# Digital_Io.net
KiCad netlist of a schematic drawn in Altium Designer
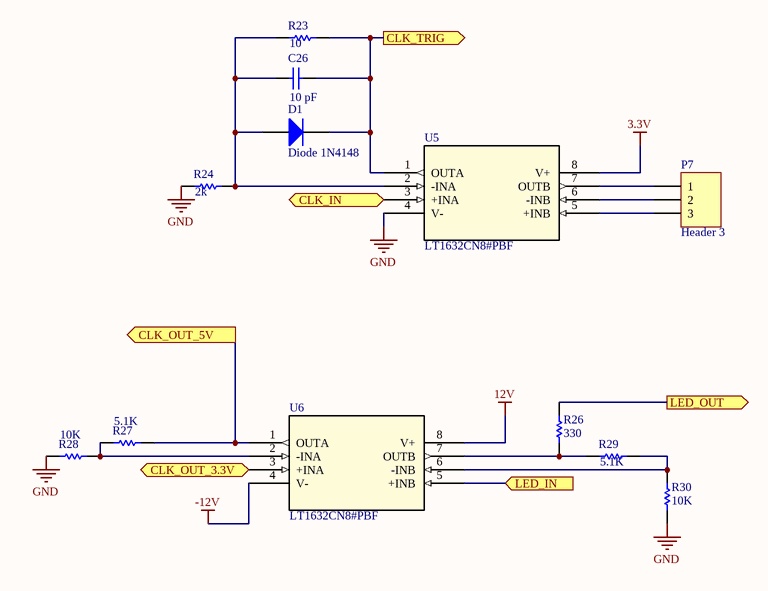
[diagram p0: Digital_Io.SchDoc]

(export (version "E")
  (design (tool "Eeschema 10.0.6"))
  (components
    (comp (ref "C26")
      (value "10 pF")
      (footprint "C0805")
      (description "Capacitor")
      (fields (field (name "PUBLISHER") "Altium Limited"))
      (libsource (lib "Miscellaneous Devices") (part "Cap"))
    )
    (comp (ref "D1")
      (value "Diode 1N4148")
      (footprint "DO-35")
      (description "High Conductance Fast Diode")
      (fields (field (name "PUBLISHER") "Altium Limited"))
      (libsource (lib "Miscellaneous Devices") (part "Diode 1N4148"))
    )
    (comp (ref "P7")
      (value "Header 3")
      (footprint "HDR1X3")
      (description "Header, 3-Pin")
      (fields (field (name "PUBLISHER") "Altium Limited"))
      (libsource (lib "Miscellaneous Connectors") (part "Header 3"))
    )
    (comp (ref "R23")
      (value "10")
      (footprint "AXIAL-0.3")
      (description "Resistor")
      (fields (field (name "Comment") "Res1") (field (name "PUBLISHER") "Altium Limited"))
      (libsource (lib "Miscellaneous Devices") (part "Res1"))
    )
    (comp (ref "R24")
      (value "2k")
      (footprint "AXIAL-0.3")
      (description "Resistor")
      (fields (field (name "Comment") "Res1") (field (name "PUBLISHER") "Altium Limited"))
      (libsource (lib "Miscellaneous Devices") (part "Res1"))
    )
    (comp (ref "R26")
      (value "330")
      (footprint "AXIAL-0.3")
      (description "Resistor")
      (fields (field (name "Comment") "Res1") (field (name "PUBLISHER") "Altium Limited"))
      (libsource (lib "Miscellaneous Devices") (part "Res1"))
    )
    (comp (ref "R27")
      (value "5.1K")
      (footprint "AXIAL-0.3")
      (description "Resistor")
      (fields (field (name "Comment") "Res1") (field (name "PUBLISHER") "Altium Limited"))
      (libsource (lib "Miscellaneous Devices") (part "Res1"))
    )
    (comp (ref "R28")
      (value "10K")
      (footprint "AXIAL-0.3")
      (description "Resistor")
      (fields (field (name "Comment") "Res1") (field (name "PUBLISHER") "Altium Limited"))
      (libsource (lib "Miscellaneous Devices") (part "Res1"))
    )
    (comp (ref "R29")
      (value "5.1K")
      (footprint "AXIAL-0.3")
      (description "Resistor")
      (fields (field (name "Comment") "Res1") (field (name "PUBLISHER") "Altium Limited"))
      (libsource (lib "Miscellaneous Devices") (part "Res1"))
    )
    (comp (ref "R30")
      (value "10K")
      (footprint "AXIAL-0.3")
      (description "Resistor")
      (fields (field (name "Comment") "Res1") (field (name "PUBLISHER") "Altium Limited"))
      (libsource (lib "Miscellaneous Devices") (part "Res1"))
    )
    (comp (ref "U5")
      (value "LT1632CN8#PBF")
      (footprint "PDIP-8_N")
      (description "Imported")
      (fields
        (field (name "DIGIKEYPARTNUMBER") "LT1632CN8-ND")
        (field (name "COPYRIGHT") "Copyright (C) 2015 Accelerated Designs. All rights reserved")
      )
      (libsource (lib "lt1632") (part "LT1632CN8#PBF"))
    )
    (comp (ref "U6")
      (value "LT1632CN8#PBF")
      (footprint "PDIP-8_N")
      (description "Imported")
      (fields
        (field (name "DIGIKEYPARTNUMBER") "LT1632CN8-ND")
        (field (name "COPYRIGHT") "Copyright (C) 2015 Accelerated Designs. All rights reserved")
      )
      (libsource (lib "lt1632") (part "LT1632CN8#PBF"))
    )
  )
  (nets
    (net (code "1") (name "-12V") (class "Default")
      (node (ref "U6") (pin "4") (pinfunction "V-_4") (pintype "power_in"))
    )
    (net (code "2") (name "/CLK_IN") (class "Default")
      (node (ref "U5") (pin "3") (pinfunction "+INA_3") (pintype "input"))
    )
    (net (code "3") (name "/CLK_OUT_3.3V") (class "Default")
      (node (ref "U6") (pin "3") (pinfunction "+INA_3") (pintype "input"))
    )
    (net (code "4") (name "/CLK_OUT_5V") (class "Default")
      (node (ref "R27") (pin "2") (pinfunction "2_2") (pintype "passive"))
      (node (ref "U6") (pin "1") (pinfunction "OUTA_1") (pintype "output"))
    )
    (net (code "5") (name "/CLK_TRIG") (class "Default")
      (node (ref "C26") (pin "1") (pinfunction "1_1") (pintype "passive"))
      (node (ref "D1") (pin "2") (pinfunction "K_2") (pintype "passive"))
      (node (ref "R23") (pin "2") (pinfunction "2_2") (pintype "passive"))
      (node (ref "U5") (pin "1") (pinfunction "OUTA_1") (pintype "output"))
    )
    (net (code "6") (name "/LED_IN") (class "Default")
      (node (ref "U6") (pin "5") (pinfunction "+INB_5") (pintype "input"))
    )
    (net (code "7") (name "/LED_OUT") (class "Default")
      (node (ref "R26") (pin "2") (pinfunction "2_2") (pintype "passive"))
    )
    (net (code "8") (name "3.3V") (class "Default")
      (node (ref "U5") (pin "8") (pinfunction "V+_8") (pintype "power_in"))
    )
    (net (code "9") (name "12V") (class "Default")
      (node (ref "U6") (pin "8") (pinfunction "V+_8") (pintype "power_in"))
    )
    (net (code "10") (name "GND") (class "Default")
      (node (ref "R24") (pin "1") (pinfunction "1_1") (pintype "passive"))
      (node (ref "R28") (pin "1") (pinfunction "1_1") (pintype "passive"))
      (node (ref "R30") (pin "1") (pinfunction "1_1") (pintype "passive"))
      (node (ref "U5") (pin "4") (pinfunction "V-_4") (pintype "power_in"))
    )
    (net (code "11") (name "Net-(D1-A)") (class "Default")
      (node (ref "C26") (pin "2") (pinfunction "2_2") (pintype "passive"))
      (node (ref "D1") (pin "1") (pinfunction "A_1") (pintype "passive"))
      (node (ref "R23") (pin "1") (pinfunction "1_1") (pintype "passive"))
      (node (ref "R24") (pin "2") (pinfunction "2_2") (pintype "passive"))
      (node (ref "U5") (pin "2") (pinfunction "-INA_2") (pintype "input"))
    )
    (net (code "12") (name "Net-(U5-+INB)") (class "Default")
      (node (ref "P7") (pin "3") (pinfunction "3_3") (pintype "passive"))
      (node (ref "U5") (pin "5") (pinfunction "+INB_5") (pintype "input"))
    )
    (net (code "13") (name "Net-(U5--INB)") (class "Default")
      (node (ref "P7") (pin "2") (pinfunction "2_2") (pintype "passive"))
      (node (ref "U5") (pin "6") (pinfunction "-INB_6") (pintype "input"))
    )
    (net (code "14") (name "Net-(U5-OUTB)") (class "Default")
      (node (ref "P7") (pin "1") (pinfunction "1_1") (pintype "passive"))
      (node (ref "U5") (pin "7") (pinfunction "OUTB_7") (pintype "output"))
    )
    (net (code "15") (name "Net-(U6--INA)") (class "Default")
      (node (ref "R27") (pin "1") (pinfunction "1_1") (pintype "passive"))
      (node (ref "R28") (pin "2") (pinfunction "2_2") (pintype "passive"))
      (node (ref "U6") (pin "2") (pinfunction "-INA_2") (pintype "input"))
    )
    (net (code "16") (name "Net-(U6--INB)") (class "Default")
      (node (ref "R29") (pin "2") (pinfunction "2_2") (pintype "passive"))
      (node (ref "R30") (pin "2") (pinfunction "2_2") (pintype "passive"))
      (node (ref "U6") (pin "6") (pinfunction "-INB_6") (pintype "input"))
    )
    (net (code "17") (name "Net-(U6-OUTB)") (class "Default")
      (node (ref "R26") (pin "1") (pinfunction "1_1") (pintype "passive"))
      (node (ref "R29") (pin "1") (pinfunction "1_1") (pintype "passive"))
      (node (ref "U6") (pin "7") (pinfunction "OUTB_7") (pintype "output"))
    )
  )
)
